# Crab_v3.net
KiCad netlist of a schematic drawn in EAGLE
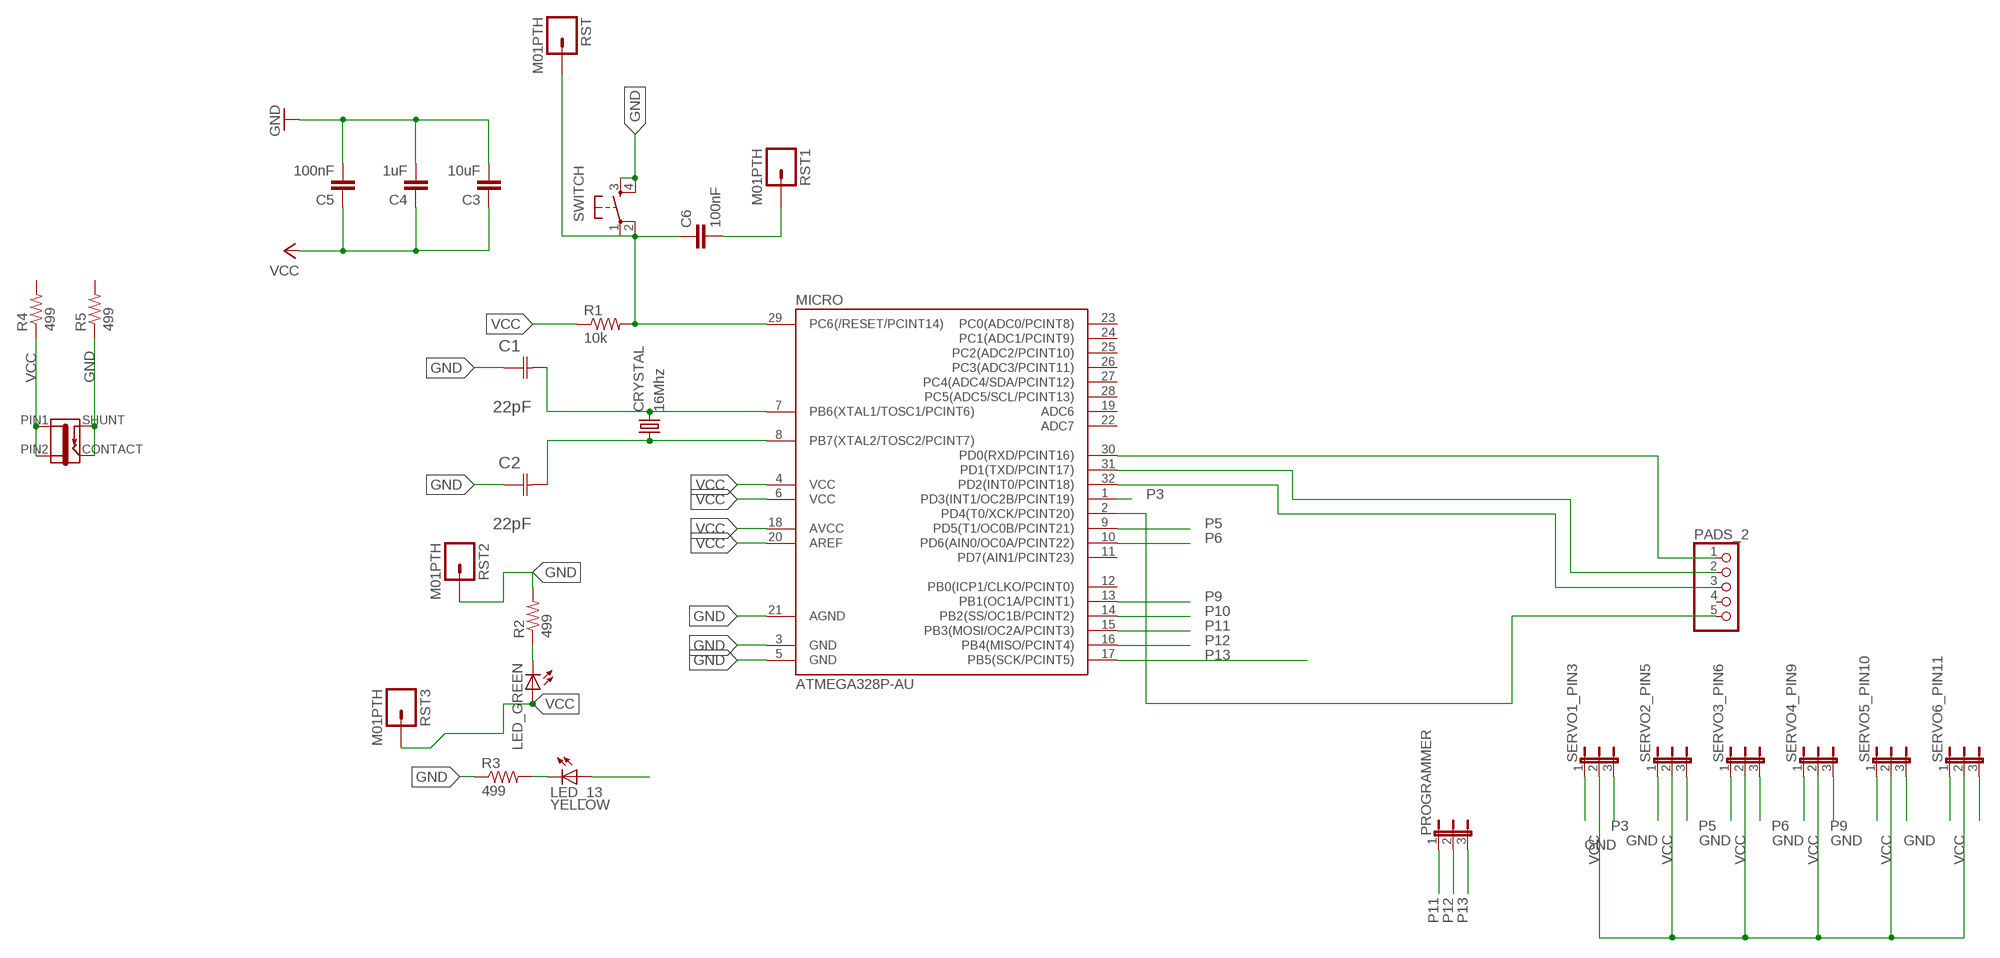
[diagram p0: schematic, sheet 1]

(export (version "E")
  (design (tool "Eeschema 10.0.6"))
  (components
    (comp (ref "C1")
      (value "22pF")
      (footprint "eagle-import:CAPC3216X178N")
      (fields (field (name "MPN") "0612ZC225MAT2A") (field (name "TOLERANCE") "±20%"))
      (libsource (lib "eagle-import") (part "0612ZC225MAT2A"))
    )
    (comp (ref "C2")
      (value "22pF")
      (footprint "eagle-import:CAPC3216X178N")
      (fields (field (name "MPN") "0612ZC225MAT2A") (field (name "TOLERANCE") "±20%"))
      (libsource (lib "eagle-import") (part "0612ZC225MAT2A"))
    )
    (comp (ref "C3")
      (value "10uF")
      (footprint "eagle-import:1206")
      (libsource (lib "eagle-import") (part "CAP1206"))
    )
    (comp (ref "C4")
      (value "1uF")
      (footprint "eagle-import:1206")
      (libsource (lib "eagle-import") (part "CAP1206"))
    )
    (comp (ref "C5")
      (value "100nF")
      (footprint "eagle-import:1206")
      (libsource (lib "eagle-import") (part "CAP1206"))
    )
    (comp (ref "C6")
      (value "100nF")
      (footprint "eagle-import:1206")
      (libsource (lib "eagle-import") (part "CAP1206"))
    )
    (comp (ref "CRYSTAL")
      (value "16Mhz")
      (footprint "eagle-import:CSM-7X-DU")
      (libsource (lib "eagle-import") (part "CSM-7X-DU"))
    )
    (comp (ref "J1")
      (value "JACK-2.1MM")
      (footprint "eagle-import:PJ-002AH-SMT")
      (libsource (lib "eagle-import") (part "JACK-2.1MM"))
    )
    (comp (ref "LED_13")
      (value "YELLOW")
      (footprint "eagle-import:1206")
      (libsource (lib "eagle-import") (part "LED1206"))
    )
    (comp (ref "LED_GREEN")
      (value "LED1206")
      (footprint "eagle-import:1206")
      (libsource (lib "eagle-import") (part "LED1206"))
    )
    (comp (ref "MICRO")
      (value "ATMEGA328P-AU")
      (footprint "eagle-import:TQFP32-08")
      (libsource (lib "eagle-import") (part "ATMEGA48/88/168-AU"))
    )
    (comp (ref "PADS_2")
      (value "PINHD-1X5")
      (footprint "eagle-import:1X05")
      (libsource (lib "eagle-import") (part "PINHD-1X5"))
    )
    (comp (ref "PROGRAMMER")
      (value "JP2E")
      (footprint "eagle-import:JP2")
      (libsource (lib "eagle-import") (part "JP2E"))
    )
    (comp (ref "R1")
      (value "10k")
      (footprint "eagle-import:1206")
      (libsource (lib "eagle-import") (part "RESISTOR1206"))
    )
    (comp (ref "R2")
      (value "499")
      (footprint "eagle-import:1206")
      (libsource (lib "eagle-import") (part "RESISTOR1206"))
    )
    (comp (ref "R3")
      (value "499")
      (footprint "eagle-import:1206")
      (libsource (lib "eagle-import") (part "RESISTOR1206"))
    )
    (comp (ref "R4")
      (value "499")
      (footprint "eagle-import:1206")
      (libsource (lib "eagle-import") (part "RESISTOR1206"))
    )
    (comp (ref "R5")
      (value "499")
      (footprint "eagle-import:1206")
      (libsource (lib "eagle-import") (part "RESISTOR1206"))
    )
    (comp (ref "RST")
      (value "M01PTH")
      (footprint "eagle-import:1X01")
      (libsource (lib "eagle-import") (part "M01PTH"))
    )
    (comp (ref "RST1")
      (value "M01PTH")
      (footprint "eagle-import:1X01")
      (libsource (lib "eagle-import") (part "M01PTH"))
    )
    (comp (ref "RST2")
      (value "M01PTH")
      (footprint "eagle-import:1X01")
      (libsource (lib "eagle-import") (part "M01PTH"))
    )
    (comp (ref "RST3")
      (value "M01PTH")
      (footprint "eagle-import:1X01")
      (libsource (lib "eagle-import") (part "M01PTH"))
    )
    (comp (ref "SERVO1_PIN3")
      (value "JP2E")
      (footprint "eagle-import:JP2")
      (libsource (lib "eagle-import") (part "JP2E"))
    )
    (comp (ref "SERVO2_PIN5")
      (value "JP2E")
      (footprint "eagle-import:JP2")
      (libsource (lib "eagle-import") (part "JP2E"))
    )
    (comp (ref "SERVO3_PIN6")
      (value "JP2E")
      (footprint "eagle-import:JP2")
      (libsource (lib "eagle-import") (part "JP2E"))
    )
    (comp (ref "SERVO4_PIN9")
      (value "JP2E")
      (footprint "eagle-import:JP2")
      (libsource (lib "eagle-import") (part "JP2E"))
    )
    (comp (ref "SERVO5_PIN10")
      (value "JP2E")
      (footprint "eagle-import:JP2")
      (libsource (lib "eagle-import") (part "JP2E"))
    )
    (comp (ref "SERVO6_PIN11")
      (value "JP2E")
      (footprint "eagle-import:JP2")
      (libsource (lib "eagle-import") (part "JP2E"))
    )
    (comp (ref "SWITCH")
      (value "6MM_SWITCH6MM_SWITCH")
      (footprint "eagle-import:6MM_SWITCH")
      (libsource (lib "eagle-import") (part "6MM_SWITCH6MM_SWITCH"))
    )
  )
  (nets
    (net (code "1") (name "/P3") (class "Default")
      (node (ref "LED_13") (pin "1") (pinfunction "A_1") (pintype "passive"))
      (node (ref "MICRO") (pin "1") (pinfunction "PD3(INT1/OC2B/PCINT19)_1") (pintype "bidirectional"))
      (node (ref "SERVO1_PIN3") (pin "3") (pinfunction "3_3") (pintype "passive"))
    )
    (net (code "2") (name "/P5") (class "Default")
      (node (ref "MICRO") (pin "9") (pinfunction "PD5(T1/OC0B/PCINT21)_9") (pintype "bidirectional"))
      (node (ref "SERVO2_PIN5") (pin "3") (pinfunction "3_3") (pintype "passive"))
    )
    (net (code "3") (name "/P6") (class "Default")
      (node (ref "MICRO") (pin "10") (pinfunction "PD6(AIN0/OC0A/PCINT22)_10") (pintype "bidirectional"))
      (node (ref "SERVO3_PIN6") (pin "3") (pinfunction "3_3") (pintype "passive"))
    )
    (net (code "4") (name "/P9") (class "Default")
      (node (ref "MICRO") (pin "13") (pinfunction "PB1(OC1A/PCINT1)_13") (pintype "bidirectional"))
      (node (ref "SERVO4_PIN9") (pin "3") (pinfunction "3_3") (pintype "passive"))
    )
    (net (code "5") (name "/P10") (class "Default")
      (node (ref "MICRO") (pin "14") (pinfunction "PB2(SS/OC1B/PCINT2)_14") (pintype "bidirectional"))
      (node (ref "SERVO5_PIN10") (pin "3") (pinfunction "3_3") (pintype "passive"))
    )
    (net (code "6") (name "/P11") (class "Default")
      (node (ref "MICRO") (pin "15") (pinfunction "PB3(MOSI/OC2A/PCINT3)_15") (pintype "bidirectional"))
      (node (ref "PROGRAMMER") (pin "1") (pinfunction "1_1") (pintype "passive"))
      (node (ref "SERVO6_PIN11") (pin "3") (pinfunction "3_3") (pintype "passive"))
    )
    (net (code "7") (name "/P12") (class "Default")
      (node (ref "MICRO") (pin "16") (pinfunction "PB4(MISO/PCINT4)_16") (pintype "bidirectional"))
      (node (ref "PROGRAMMER") (pin "2") (pinfunction "2_2") (pintype "passive"))
    )
    (net (code "8") (name "/P13") (class "Default")
      (node (ref "MICRO") (pin "17") (pinfunction "PB5(SCK/PCINT5)_17") (pintype "bidirectional"))
      (node (ref "PROGRAMMER") (pin "3") (pinfunction "3_3") (pintype "passive"))
    )
    (net (code "9") (name "GND") (class "Default")
      (node (ref "C1") (pin "1") (pinfunction "C1_1") (pintype "passive"))
      (node (ref "C2") (pin "1") (pinfunction "C1_1") (pintype "passive"))
      (node (ref "C3") (pin "2") (pinfunction "2_2") (pintype "passive"))
      (node (ref "C4") (pin "2") (pinfunction "2_2") (pintype "passive"))
      (node (ref "C5") (pin "2") (pinfunction "2_2") (pintype "passive"))
      (node (ref "J1") (pin "CONTACT") (pinfunction "CONTACT_CONTACT") (pintype "power_in"))
      (node (ref "J1") (pin "SHUNT") (pinfunction "SHUNT_SHUNT") (pintype "power_in"))
      (node (ref "MICRO") (pin "21") (pinfunction "AGND_21") (pintype "power_in"))
      (node (ref "MICRO") (pin "3") (pinfunction "GND_3") (pintype "power_in"))
      (node (ref "MICRO") (pin "5") (pinfunction "GND_5") (pintype "power_in"))
      (node (ref "R2") (pin "2") (pinfunction "2_2") (pintype "passive"))
      (node (ref "R3") (pin "1") (pinfunction "1_1") (pintype "passive"))
      (node (ref "R5") (pin "1") (pinfunction "1_1") (pintype "passive"))
      (node (ref "RST2") (pin "1") (pinfunction "1_1") (pintype "passive"))
      (node (ref "SERVO1_PIN3") (pin "1") (pinfunction "1_1") (pintype "passive"))
      (node (ref "SERVO2_PIN5") (pin "1") (pinfunction "1_1") (pintype "passive"))
      (node (ref "SERVO3_PIN6") (pin "1") (pinfunction "1_1") (pintype "passive"))
      (node (ref "SERVO4_PIN9") (pin "1") (pinfunction "1_1") (pintype "passive"))
      (node (ref "SERVO5_PIN10") (pin "1") (pinfunction "1_1") (pintype "passive"))
      (node (ref "SERVO6_PIN11") (pin "1") (pinfunction "1_1") (pintype "passive"))
      (node (ref "SWITCH") (pin "3") (pinfunction "S_3") (pintype "passive"))
      (node (ref "SWITCH") (pin "4") (pinfunction "S1_4") (pintype "passive"))
    )
    (net (code "10") (name "Net-(C1-C2)") (class "Default")
      (node (ref "C1") (pin "2") (pinfunction "C2_2") (pintype "passive"))
      (node (ref "CRYSTAL") (pin "2") (pinfunction "2_2") (pintype "passive"))
      (node (ref "MICRO") (pin "7") (pinfunction "PB6(XTAL1/TOSC1/PCINT6)_7") (pintype "bidirectional"))
    )
    (net (code "11") (name "Net-(C2-C2)") (class "Default")
      (node (ref "C2") (pin "2") (pinfunction "C2_2") (pintype "passive"))
      (node (ref "CRYSTAL") (pin "1") (pinfunction "1_1") (pintype "passive"))
      (node (ref "MICRO") (pin "8") (pinfunction "PB7(XTAL2/TOSC2/PCINT7)_8") (pintype "bidirectional"))
    )
    (net (code "12") (name "Net-(C6-Pad2)") (class "Default")
      (node (ref "C6") (pin "2") (pinfunction "2_2") (pintype "passive"))
      (node (ref "RST1") (pin "1") (pinfunction "1_1") (pintype "passive"))
    )
    (net (code "13") (name "Net-(LED_13-C)") (class "Default")
      (node (ref "LED_13") (pin "2") (pinfunction "C_2") (pintype "passive"))
      (node (ref "R3") (pin "2") (pinfunction "2_2") (pintype "passive"))
    )
    (net (code "14") (name "Net-(LED_GREEN-C)") (class "Default")
      (node (ref "LED_GREEN") (pin "2") (pinfunction "C_2") (pintype "passive"))
      (node (ref "R2") (pin "1") (pinfunction "1_1") (pintype "passive"))
    )
    (net (code "15") (name "Net-(MICRO-PC6({slash}RESET{slash}PCINT14))") (class "Default")
      (node (ref "C6") (pin "1") (pinfunction "1_1") (pintype "passive"))
      (node (ref "MICRO") (pin "29") (pinfunction "PC6(/RESET/PCINT14)_29") (pintype "bidirectional"))
      (node (ref "R1") (pin "2") (pinfunction "2_2") (pintype "passive"))
      (node (ref "RST") (pin "1") (pinfunction "1_1") (pintype "passive"))
      (node (ref "SWITCH") (pin "1") (pinfunction "P_1") (pintype "passive"))
      (node (ref "SWITCH") (pin "2") (pinfunction "P1_2") (pintype "passive"))
    )
    (net (code "16") (name "Net-(MICRO-PD0(RXD{slash}PCINT16))") (class "Default")
      (node (ref "MICRO") (pin "30") (pinfunction "PD0(RXD/PCINT16)_30") (pintype "bidirectional"))
      (node (ref "PADS_2") (pin "1") (pinfunction "1_1") (pintype "passive"))
    )
    (net (code "17") (name "Net-(MICRO-PD1(TXD{slash}PCINT17))") (class "Default")
      (node (ref "MICRO") (pin "31") (pinfunction "PD1(TXD/PCINT17)_31") (pintype "bidirectional"))
      (node (ref "PADS_2") (pin "2") (pinfunction "2_2") (pintype "passive"))
    )
    (net (code "18") (name "Net-(MICRO-PD2(INT0{slash}PCINT18))") (class "Default")
      (node (ref "MICRO") (pin "32") (pinfunction "PD2(INT0/PCINT18)_32") (pintype "bidirectional"))
      (node (ref "PADS_2") (pin "3") (pinfunction "3_3") (pintype "passive"))
    )
    (net (code "19") (name "Net-(MICRO-PD4(T0{slash}XCK{slash}PCINT20))") (class "Default")
      (node (ref "MICRO") (pin "2") (pinfunction "PD4(T0/XCK/PCINT20)_2") (pintype "bidirectional"))
      (node (ref "PADS_2") (pin "5") (pinfunction "5_5") (pintype "passive"))
    )
    (net (code "20") (name "VCC") (class "Default")
      (node (ref "C3") (pin "1") (pinfunction "1_1") (pintype "passive"))
      (node (ref "C4") (pin "1") (pinfunction "1_1") (pintype "passive"))
      (node (ref "C5") (pin "1") (pinfunction "1_1") (pintype "passive"))
      (node (ref "J1") (pin "PIN1") (pinfunction "PIN1_PIN1") (pintype "power_in"))
      (node (ref "J1") (pin "PIN2") (pinfunction "PIN2_PIN2") (pintype "power_in"))
      (node (ref "LED_GREEN") (pin "1") (pinfunction "A_1") (pintype "passive"))
      (node (ref "MICRO") (pin "18") (pinfunction "AVCC_18") (pintype "passive"))
      (node (ref "MICRO") (pin "20") (pinfunction "AREF_20") (pintype "passive"))
      (node (ref "MICRO") (pin "4") (pinfunction "VCC_4") (pintype "power_in"))
      (node (ref "MICRO") (pin "6") (pinfunction "VCC_6") (pintype "power_in"))
      (node (ref "R1") (pin "1") (pinfunction "1_1") (pintype "passive"))
      (node (ref "R4") (pin "1") (pinfunction "1_1") (pintype "passive"))
      (node (ref "RST3") (pin "1") (pinfunction "1_1") (pintype "passive"))
      (node (ref "SERVO1_PIN3") (pin "2") (pinfunction "2_2") (pintype "passive"))
      (node (ref "SERVO2_PIN5") (pin "2") (pinfunction "2_2") (pintype "passive"))
      (node (ref "SERVO3_PIN6") (pin "2") (pinfunction "2_2") (pintype "passive"))
      (node (ref "SERVO4_PIN9") (pin "2") (pinfunction "2_2") (pintype "passive"))
      (node (ref "SERVO5_PIN10") (pin "2") (pinfunction "2_2") (pintype "passive"))
      (node (ref "SERVO6_PIN11") (pin "2") (pinfunction "2_2") (pintype "passive"))
    )
    (net (code "21") (name "unconnected-(MICRO-ADC6-Pad19)") (class "Default")
      (node (ref "MICRO") (pin "19") (pinfunction "ADC6_19") (pintype "passive"))
    )
    (net (code "22") (name "unconnected-(MICRO-ADC7-Pad22)") (class "Default")
      (node (ref "MICRO") (pin "22") (pinfunction "ADC7_22") (pintype "passive"))
    )
    (net (code "23") (name "unconnected-(MICRO-PB0(ICP1{slash}CLKO{slash}PCINT0)-Pad12)") (class "Default")
      (node (ref "MICRO") (pin "12") (pinfunction "PB0(ICP1/CLKO/PCINT0)_12") (pintype "bidirectional"))
    )
    (net (code "24") (name "unconnected-(MICRO-PC0(ADC0{slash}PCINT8)-Pad23)") (class "Default")
      (node (ref "MICRO") (pin "23") (pinfunction "PC0(ADC0/PCINT8)_23") (pintype "bidirectional"))
    )
    (net (code "25") (name "unconnected-(MICRO-PC1(ADC1{slash}PCINT9)-Pad24)") (class "Default")
      (node (ref "MICRO") (pin "24") (pinfunction "PC1(ADC1/PCINT9)_24") (pintype "bidirectional"))
    )
    (net (code "26") (name "unconnected-(MICRO-PC2(ADC2{slash}PCINT10)-Pad25)") (class "Default")
      (node (ref "MICRO") (pin "25") (pinfunction "PC2(ADC2/PCINT10)_25") (pintype "bidirectional"))
    )
    (net (code "27") (name "unconnected-(MICRO-PC3(ADC3{slash}PCINT11)-Pad26)") (class "Default")
      (node (ref "MICRO") (pin "26") (pinfunction "PC3(ADC3/PCINT11)_26") (pintype "bidirectional"))
    )
    (net (code "28") (name "unconnected-(MICRO-PC4(ADC4{slash}SDA{slash}PCINT12)-Pad27)") (class "Default")
      (node (ref "MICRO") (pin "27") (pinfunction "PC4(ADC4/SDA/PCINT12)_27") (pintype "bidirectional"))
    )
    (net (code "29") (name "unconnected-(MICRO-PC5(ADC5{slash}SCL{slash}PCINT13)-Pad28)") (class "Default")
      (node (ref "MICRO") (pin "28") (pinfunction "PC5(ADC5/SCL/PCINT13)_28") (pintype "bidirectional"))
    )
    (net (code "30") (name "unconnected-(MICRO-PD7(AIN1{slash}PCINT23)-Pad11)") (class "Default")
      (node (ref "MICRO") (pin "11") (pinfunction "PD7(AIN1/PCINT23)_11") (pintype "bidirectional"))
    )
    (net (code "31") (name "unconnected-(PADS_2-Pad4)") (class "Default")
      (node (ref "PADS_2") (pin "4") (pinfunction "4_4") (pintype "passive"))
    )
    (net (code "32") (name "unconnected-(R4-Pad2)") (class "Default")
      (node (ref "R4") (pin "2") (pinfunction "2_2") (pintype "passive"))
    )
    (net (code "33") (name "unconnected-(R5-Pad2)") (class "Default")
      (node (ref "R5") (pin "2") (pinfunction "2_2") (pintype "passive"))
    )
  )
)
